# Instrumentation_Amplifier.net
KiCad netlist of a schematic drawn in EasyEDA Pro
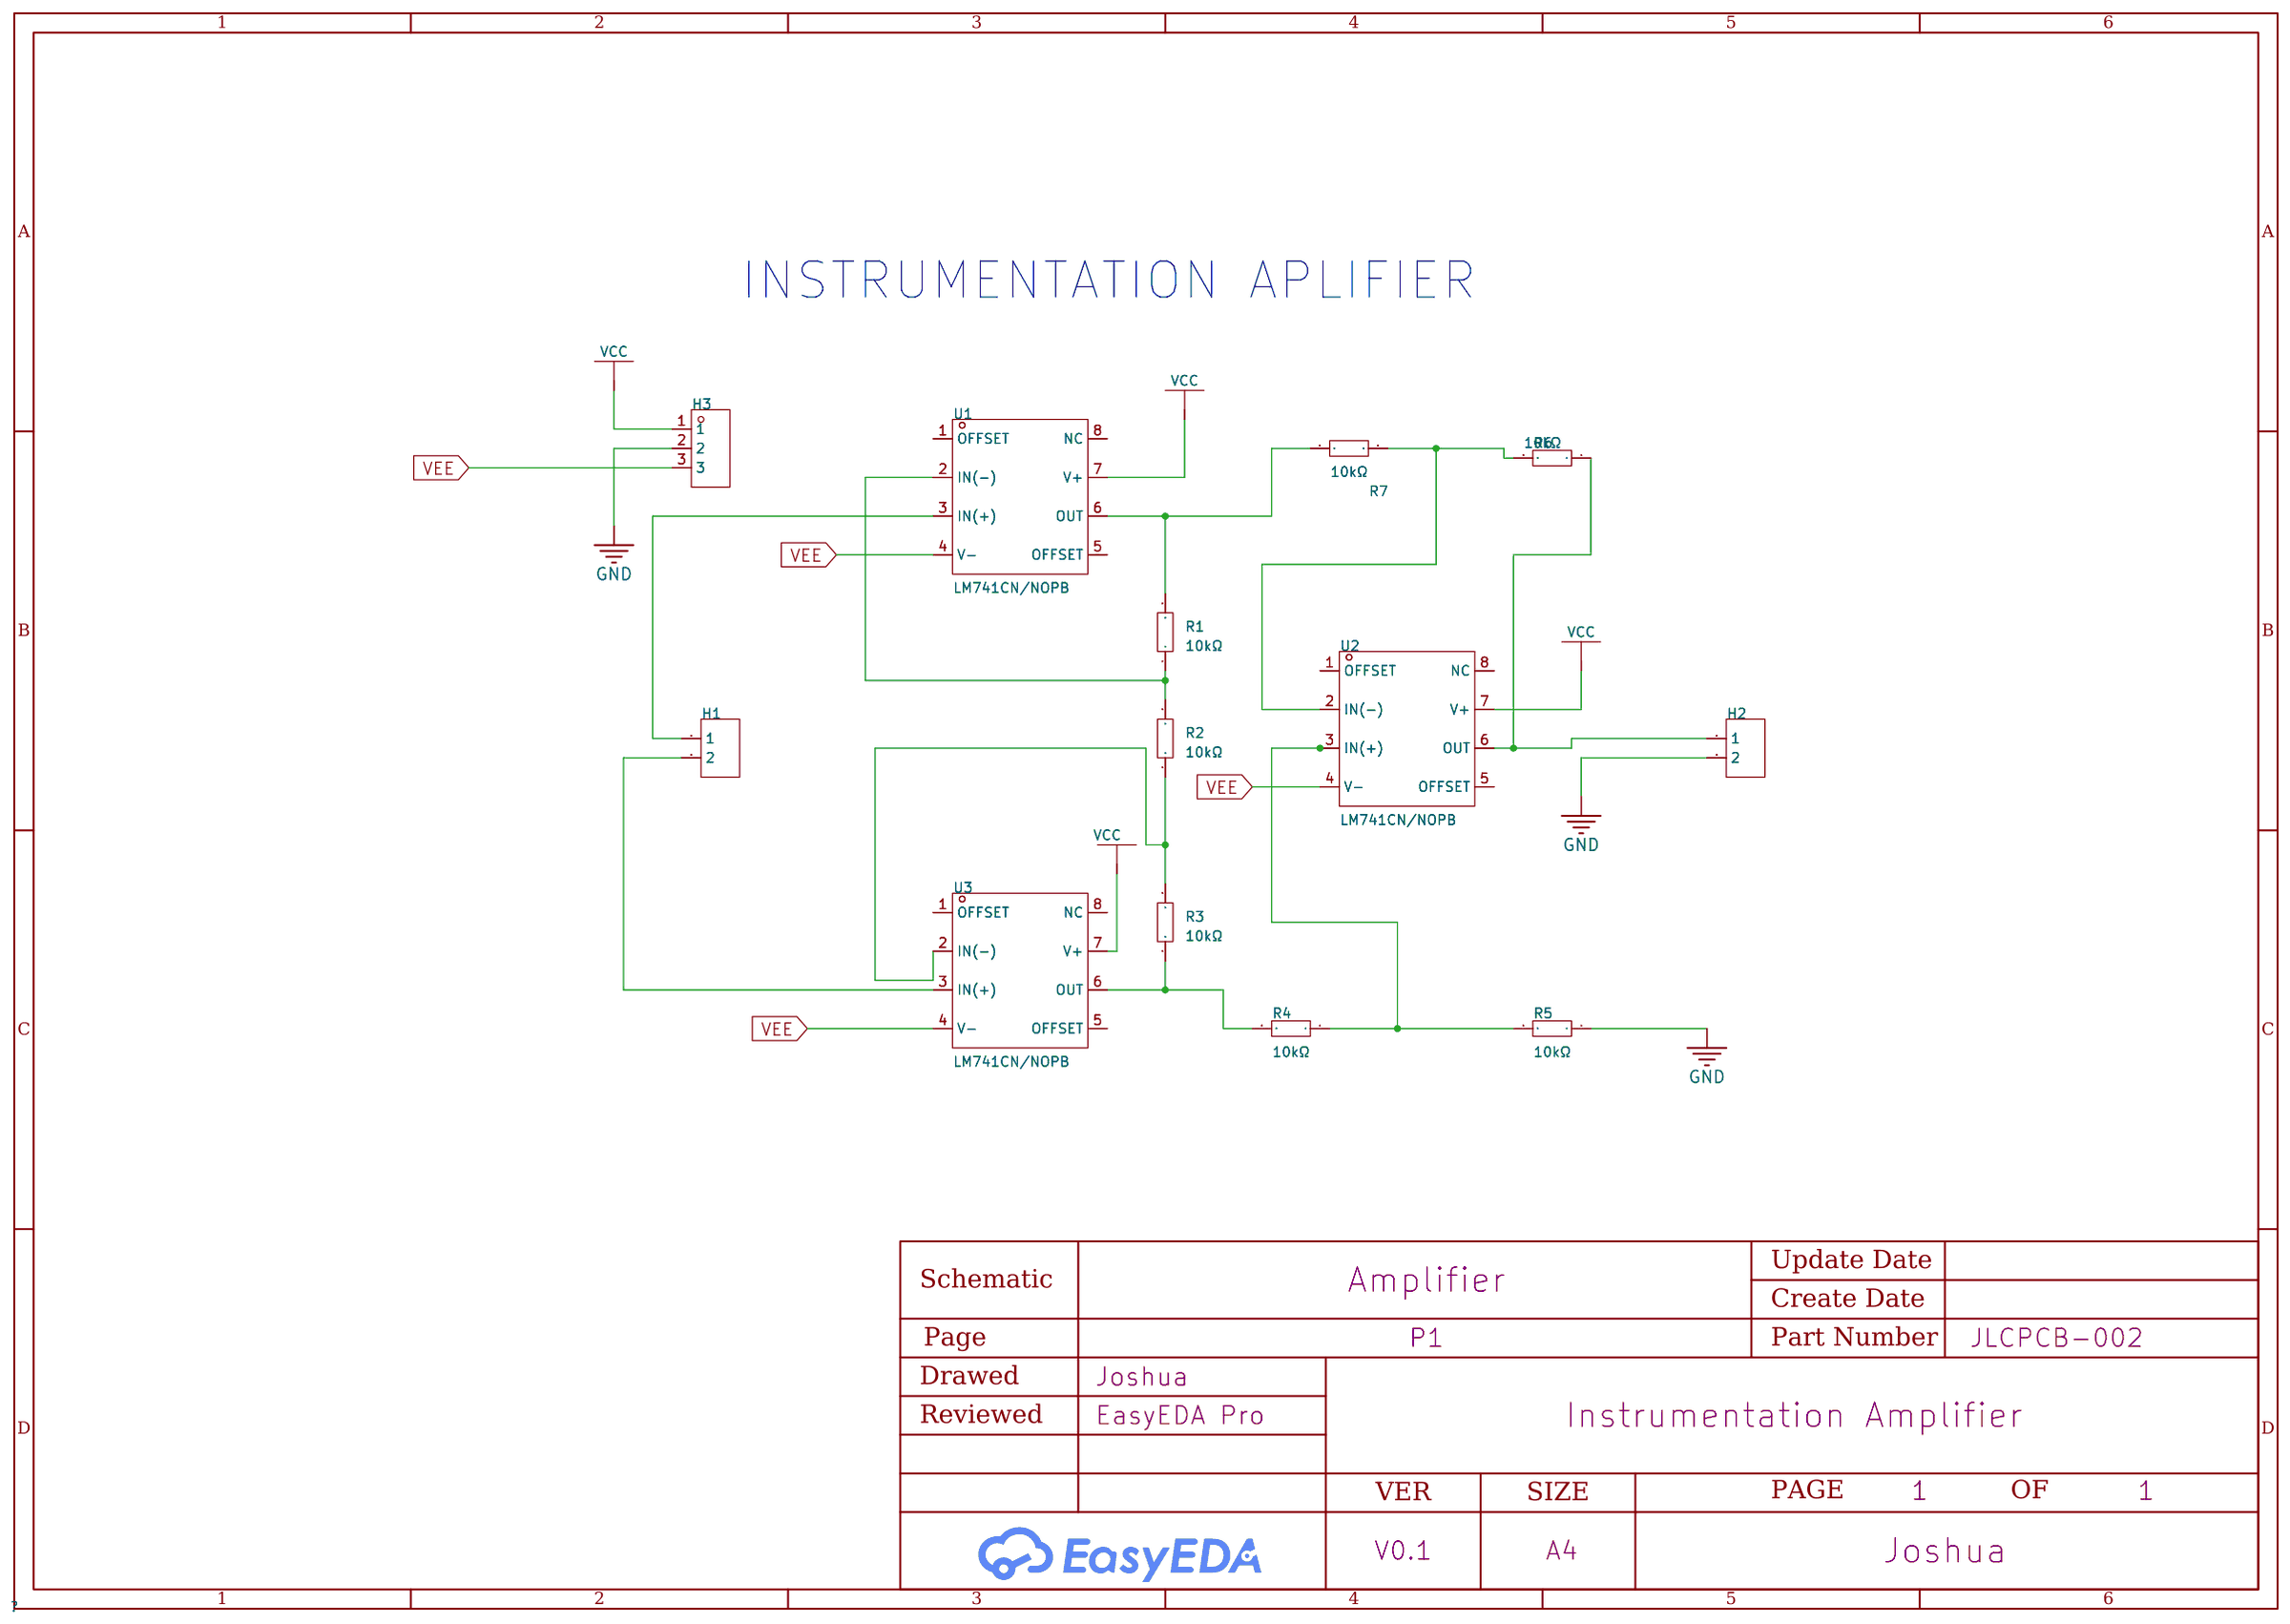
[diagram p0: schematic sheet]

(export (version "E")
  (design (tool "Eeschema 10.0.6"))
  (components
    (comp (ref "H1")
      (value "~")
      (footprint "easyedapro:HDR-TH_2P-P2.54-V-F")
      (libsource (lib "easyedapro") (part "Header-Female-2.54_1x2"))
    )
    (comp (ref "H2")
      (value "~")
      (footprint "easyedapro:HDR-TH_2P-P2.54-V-F")
      (libsource (lib "easyedapro") (part "Header-Female-2.54_1x2"))
    )
    (comp (ref "H3")
      (value "~")
      (footprint "easyedapro:HDR-TH_3P-P2.54-V-F")
      (libsource (lib "easyedapro") (part "PM254V-11-03-H85"))
    )
    (comp (ref "R1")
      (value "10kΩ")
      (footprint "easyedapro:RES-TH_BD3.3-L9.0-P13.00-D0.6")
      (libsource (lib "easyedapro") (part "Res"))
    )
    (comp (ref "R2")
      (value "10kΩ")
      (footprint "easyedapro:RES-TH_BD3.3-L9.0-P13.00-D0.6")
      (libsource (lib "easyedapro") (part "Res"))
    )
    (comp (ref "R3")
      (value "10kΩ")
      (footprint "easyedapro:RES-TH_BD3.3-L9.0-P13.00-D0.6")
      (libsource (lib "easyedapro") (part "Res"))
    )
    (comp (ref "R4")
      (value "10kΩ")
      (footprint "easyedapro:RES-TH_BD3.3-L9.0-P13.00-D0.6")
      (libsource (lib "easyedapro") (part "Res"))
    )
    (comp (ref "R5")
      (value "10kΩ")
      (footprint "easyedapro:RES-TH_BD3.3-L9.0-P13.00-D0.6")
      (libsource (lib "easyedapro") (part "Res"))
    )
    (comp (ref "R6")
      (value "10kΩ")
      (footprint "easyedapro:RES-TH_BD3.3-L9.0-P13.00-D0.6")
      (libsource (lib "easyedapro") (part "Res"))
    )
    (comp (ref "R7")
      (value "10kΩ")
      (footprint "easyedapro:RES-TH_BD3.3-L9.0-P13.00-D0.6")
      (libsource (lib "easyedapro") (part "Res"))
    )
    (comp (ref "U1")
      (value "LM741CN/NOPB")
      (footprint "easyedapro:DIP-8_L9.8-W6.6-P2.54-LS7.6-BL")
      (fields (field (name "Manufacturer") "TI(德州仪器)"))
      (libsource (lib "easyedapro") (part "LM741CN"))
    )
    (comp (ref "U2")
      (value "LM741CN/NOPB")
      (footprint "easyedapro:DIP-8_L9.8-W6.6-P2.54-LS7.6-BL")
      (fields (field (name "Manufacturer") "TI(德州仪器)"))
      (libsource (lib "easyedapro") (part "LM741CN"))
    )
    (comp (ref "U3")
      (value "LM741CN/NOPB")
      (footprint "easyedapro:DIP-8_L9.8-W6.6-P2.54-LS7.6-BL")
      (fields (field (name "Manufacturer") "TI(德州仪器)"))
      (libsource (lib "easyedapro") (part "LM741CN"))
    )
  )
  (nets
    (net (code "1") (name "GND") (class "Default")
      (node (ref "H2") (pin "2") (pinfunction "2_2") (pintype "input"))
      (node (ref "H3") (pin "2") (pinfunction "2_2") (pintype "input"))
      (node (ref "R5") (pin "1") (pinfunction "1_1") (pintype "input"))
    )
    (net (code "2") (name "Net-(U1-IN(+))") (class "Default")
      (node (ref "H1") (pin "1") (pinfunction "1_1") (pintype "input"))
      (node (ref "U1") (pin "3") (pinfunction "IN(+)_3") (pintype "input"))
    )
    (net (code "3") (name "Net-(U1-IN(-))") (class "Default")
      (node (ref "R1") (pin "1") (pinfunction "1_1") (pintype "input"))
      (node (ref "R2") (pin "2") (pinfunction "2_2") (pintype "input"))
      (node (ref "U1") (pin "2") (pinfunction "IN(-)_2") (pintype "input"))
    )
    (net (code "4") (name "Net-(U1-OUT)") (class "Default")
      (node (ref "R1") (pin "2") (pinfunction "2_2") (pintype "input"))
      (node (ref "R7") (pin "2") (pinfunction "2_2") (pintype "input"))
      (node (ref "U1") (pin "6") (pinfunction "OUT_6") (pintype "input"))
    )
    (net (code "5") (name "Net-(U2-IN(+))") (class "Default")
      (node (ref "R4") (pin "1") (pinfunction "1_1") (pintype "input"))
      (node (ref "R5") (pin "2") (pinfunction "2_2") (pintype "input"))
      (node (ref "U2") (pin "3") (pinfunction "IN(+)_3") (pintype "input"))
    )
    (net (code "6") (name "Net-(U2-IN(-))") (class "Default")
      (node (ref "R6") (pin "2") (pinfunction "2_2") (pintype "input"))
      (node (ref "R7") (pin "1") (pinfunction "1_1") (pintype "input"))
      (node (ref "U2") (pin "2") (pinfunction "IN(-)_2") (pintype "input"))
    )
    (net (code "7") (name "Net-(U2-OUT)") (class "Default")
      (node (ref "H2") (pin "1") (pinfunction "1_1") (pintype "input"))
      (node (ref "R6") (pin "1") (pinfunction "1_1") (pintype "input"))
      (node (ref "U2") (pin "6") (pinfunction "OUT_6") (pintype "input"))
    )
    (net (code "8") (name "Net-(U3-IN(+))") (class "Default")
      (node (ref "H1") (pin "2") (pinfunction "2_2") (pintype "input"))
      (node (ref "U3") (pin "3") (pinfunction "IN(+)_3") (pintype "input"))
    )
    (net (code "9") (name "Net-(U3-IN(-))") (class "Default")
      (node (ref "R2") (pin "1") (pinfunction "1_1") (pintype "input"))
      (node (ref "R3") (pin "2") (pinfunction "2_2") (pintype "input"))
      (node (ref "U3") (pin "2") (pinfunction "IN(-)_2") (pintype "input"))
    )
    (net (code "10") (name "Net-(U3-OUT)") (class "Default")
      (node (ref "R3") (pin "1") (pinfunction "1_1") (pintype "input"))
      (node (ref "R4") (pin "2") (pinfunction "2_2") (pintype "input"))
      (node (ref "U3") (pin "6") (pinfunction "OUT_6") (pintype "input"))
    )
    (net (code "11") (name "VCC") (class "Default")
      (node (ref "H3") (pin "1") (pinfunction "1_1") (pintype "input"))
      (node (ref "U1") (pin "7") (pinfunction "V+_7") (pintype "input"))
      (node (ref "U2") (pin "7") (pinfunction "V+_7") (pintype "input"))
      (node (ref "U3") (pin "7") (pinfunction "V+_7") (pintype "input"))
    )
    (net (code "12") (name "VEE") (class "Default")
      (node (ref "H3") (pin "3") (pinfunction "3_3") (pintype "input"))
      (node (ref "U1") (pin "4") (pinfunction "V-_4") (pintype "input"))
      (node (ref "U2") (pin "4") (pinfunction "V-_4") (pintype "input"))
      (node (ref "U3") (pin "4") (pinfunction "V-_4") (pintype "input"))
    )
    (net (code "13") (name "unconnected-(U1-NC-Pad8)") (class "Default")
      (node (ref "U1") (pin "8") (pinfunction "NC_8") (pintype "input"))
    )
    (net (code "14") (name "unconnected-(U1-OFFSET-Pad1)") (class "Default")
      (node (ref "U1") (pin "1") (pinfunction "OFFSET_1") (pintype "input"))
    )
    (net (code "15") (name "unconnected-(U1-OFFSET-Pad5)") (class "Default")
      (node (ref "U1") (pin "5") (pinfunction "OFFSET_5") (pintype "input"))
    )
    (net (code "16") (name "unconnected-(U2-NC-Pad8)") (class "Default")
      (node (ref "U2") (pin "8") (pinfunction "NC_8") (pintype "input"))
    )
    (net (code "17") (name "unconnected-(U2-OFFSET-Pad1)") (class "Default")
      (node (ref "U2") (pin "1") (pinfunction "OFFSET_1") (pintype "input"))
    )
    (net (code "18") (name "unconnected-(U2-OFFSET-Pad5)") (class "Default")
      (node (ref "U2") (pin "5") (pinfunction "OFFSET_5") (pintype "input"))
    )
    (net (code "19") (name "unconnected-(U3-NC-Pad8)") (class "Default")
      (node (ref "U3") (pin "8") (pinfunction "NC_8") (pintype "input"))
    )
    (net (code "20") (name "unconnected-(U3-OFFSET-Pad1)") (class "Default")
      (node (ref "U3") (pin "1") (pinfunction "OFFSET_1") (pintype "input"))
    )
    (net (code "21") (name "unconnected-(U3-OFFSET-Pad5)") (class "Default")
      (node (ref "U3") (pin "5") (pinfunction "OFFSET_5") (pintype "input"))
    )
  )
)
